# Keyboard_Joy.net
KiCad netlist of a schematic drawn in Altium Designer
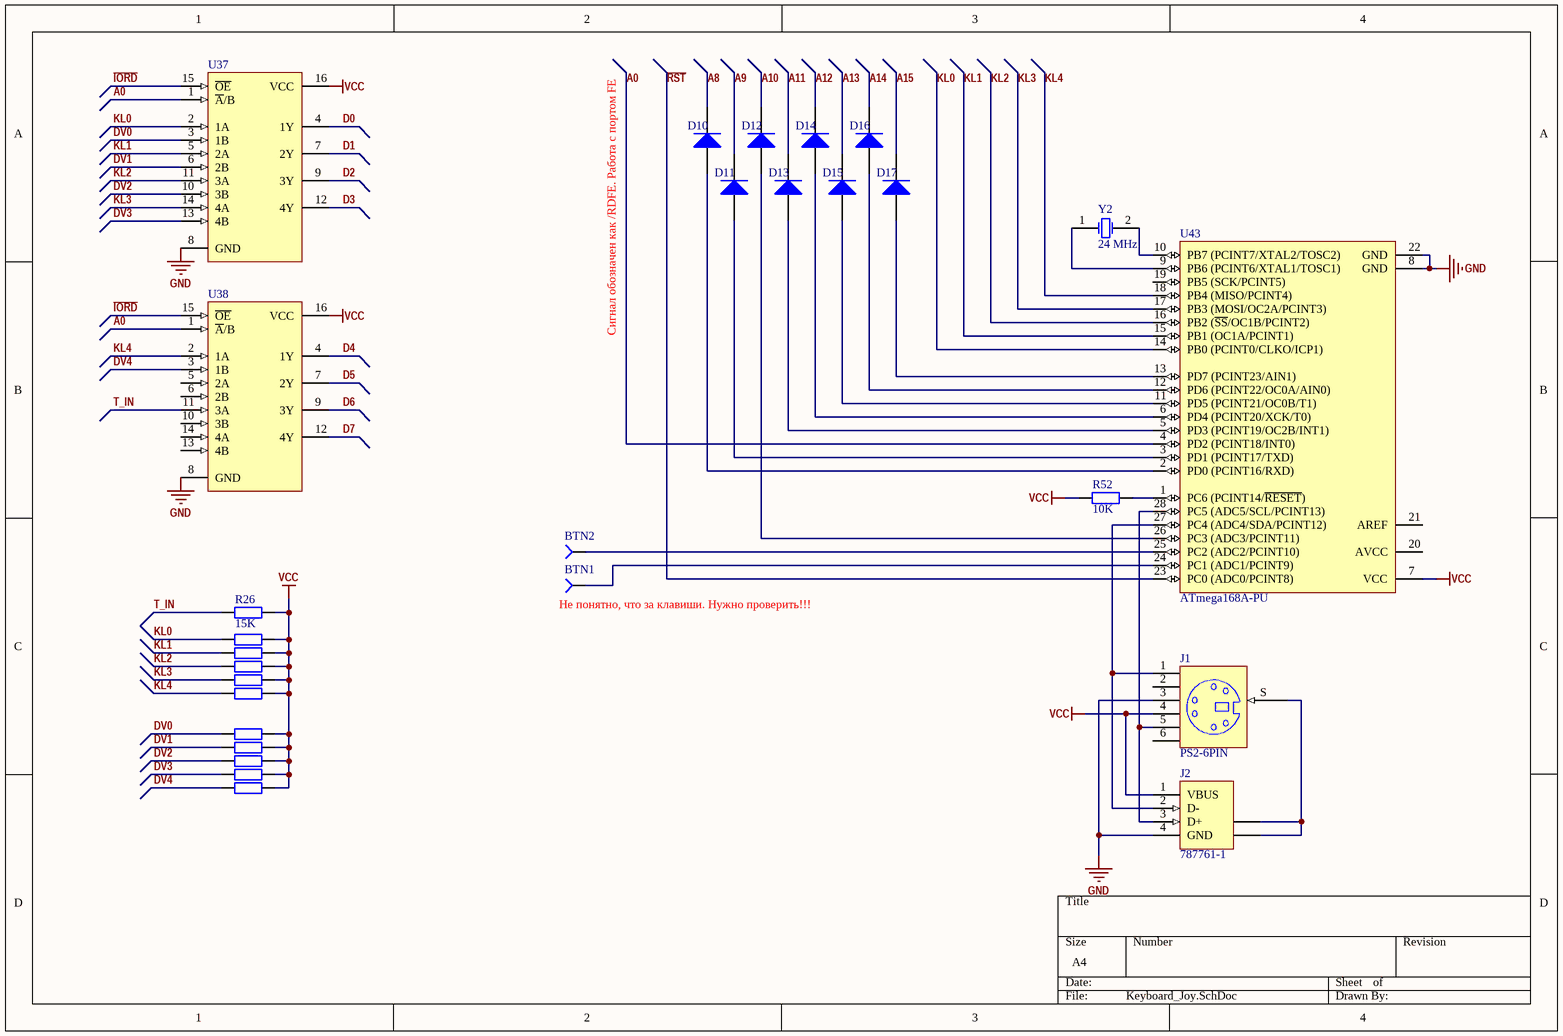
[diagram p0: Keyboard_Joy.SchDoc]

(export (version "E")
  (design (tool "Eeschema 10.0.6"))
  (components
    (comp (ref "BTN1")
      (value "Socket")
      (footprint "PIN1")
      (fields (field (name "PUBLISHER") "Altium Limited"))
      (libsource (lib "Lenin") (part "Socket"))
    )
    (comp (ref "BTN2")
      (value "Socket")
      (footprint "PIN1")
      (fields (field (name "PUBLISHER") "Altium Limited"))
      (libsource (lib "Lenin") (part "Socket"))
    )
    (comp (ref "D10")
      (value "Diode 1N4148")
      (footprint "DO-35")
      (description "High Conductance Fast Diode")
      (fields (field (name "PUBLISHER") "Altium Limited"))
      (libsource (lib "Miscellaneous Devices") (part "Diode 1N4148"))
    )
    (comp (ref "D11")
      (value "Diode 1N4148")
      (footprint "DO-35")
      (description "High Conductance Fast Diode")
      (fields (field (name "PUBLISHER") "Altium Limited"))
      (libsource (lib "Miscellaneous Devices") (part "Diode 1N4148"))
    )
    (comp (ref "D12")
      (value "Diode 1N4148")
      (footprint "DO-35")
      (description "High Conductance Fast Diode")
      (fields (field (name "PUBLISHER") "Altium Limited"))
      (libsource (lib "Miscellaneous Devices") (part "Diode 1N4148"))
    )
    (comp (ref "D13")
      (value "Diode 1N4148")
      (footprint "DO-35")
      (description "High Conductance Fast Diode")
      (fields (field (name "PUBLISHER") "Altium Limited"))
      (libsource (lib "Miscellaneous Devices") (part "Diode 1N4148"))
    )
    (comp (ref "D14")
      (value "Diode 1N4148")
      (footprint "DO-35")
      (description "High Conductance Fast Diode")
      (fields (field (name "PUBLISHER") "Altium Limited"))
      (libsource (lib "Miscellaneous Devices") (part "Diode 1N4148"))
    )
    (comp (ref "D15")
      (value "Diode 1N4148")
      (footprint "DO-35")
      (description "High Conductance Fast Diode")
      (fields (field (name "PUBLISHER") "Altium Limited"))
      (libsource (lib "Miscellaneous Devices") (part "Diode 1N4148"))
    )
    (comp (ref "D16")
      (value "Diode 1N4148")
      (footprint "DO-35")
      (description "High Conductance Fast Diode")
      (fields (field (name "PUBLISHER") "Altium Limited"))
      (libsource (lib "Miscellaneous Devices") (part "Diode 1N4148"))
    )
    (comp (ref "D17")
      (value "Diode 1N4148")
      (footprint "DO-35")
      (description "High Conductance Fast Diode")
      (fields (field (name "PUBLISHER") "Altium Limited"))
      (libsource (lib "Miscellaneous Devices") (part "Diode 1N4148"))
    )
    (comp (ref "J1")
      (value "PS2-6PIN")
      (footprint "PS2-6PIN")
      (description "6 Pin Through Hole PS2 Socket (Kycon P/N)")
      (fields (field (name "PUBLISHER") "Altium Limited"))
      (libsource (lib "Miscellaneous Connectors") (part "PS2-6PIN"))
    )
    (comp (ref "J2")
      (value "787761-1")
      (footprint "787761")
      (description "USB 1.1, Right Angle, Thru-Hole, A Type, Receptacle, 4 Position, Black")
      (fields (field (name "PUBLISHER") "Altium Limited"))
      (libsource (lib "AMP Serial Bus USB") (part "787761-1"))
    )
    (comp (ref "R26")
      (value "15K")
      (footprint "Lenin:AXIAL-0.4")
      (description "Resistor")
      (fields (field (name "Comment") "Res2") (field (name "PUBLISHER") "Altium Limited"))
      (libsource (lib "Lenin") (part "Res2"))
    )
    (comp (ref "R27")
      (value "Res2")
      (footprint "Lenin:AXIAL-0.4")
      (description "Resistor")
      (fields (field (name "PUBLISHER") "Altium Limited"))
      (libsource (lib "Lenin") (part "Res2"))
    )
    (comp (ref "R28")
      (value "Res2")
      (footprint "Lenin:AXIAL-0.4")
      (description "Resistor")
      (fields (field (name "PUBLISHER") "Altium Limited"))
      (libsource (lib "Lenin") (part "Res2"))
    )
    (comp (ref "R29")
      (value "Res2")
      (footprint "Lenin:AXIAL-0.4")
      (description "Resistor")
      (fields (field (name "PUBLISHER") "Altium Limited"))
      (libsource (lib "Lenin") (part "Res2"))
    )
    (comp (ref "R30")
      (value "Res2")
      (footprint "Lenin:AXIAL-0.4")
      (description "Resistor")
      (fields (field (name "PUBLISHER") "Altium Limited"))
      (libsource (lib "Lenin") (part "Res2"))
    )
    (comp (ref "R33")
      (value "Res2")
      (footprint "Lenin:AXIAL-0.4")
      (description "Resistor")
      (fields (field (name "PUBLISHER") "Altium Limited"))
      (libsource (lib "Lenin") (part "Res2"))
    )
    (comp (ref "R36")
      (value "Res2")
      (footprint "Lenin:AXIAL-0.4")
      (description "Resistor")
      (fields (field (name "PUBLISHER") "Altium Limited"))
      (libsource (lib "Lenin") (part "Res2"))
    )
    (comp (ref "R38")
      (value "Res2")
      (footprint "Lenin:AXIAL-0.4")
      (description "Resistor")
      (fields (field (name "PUBLISHER") "Altium Limited"))
      (libsource (lib "Lenin") (part "Res2"))
    )
    (comp (ref "R40")
      (value "Res2")
      (footprint "Lenin:AXIAL-0.4")
      (description "Resistor")
      (fields (field (name "PUBLISHER") "Altium Limited"))
      (libsource (lib "Lenin") (part "Res2"))
    )
    (comp (ref "R42")
      (value "Res2")
      (footprint "Lenin:AXIAL-0.4")
      (description "Resistor")
      (fields (field (name "PUBLISHER") "Altium Limited"))
      (libsource (lib "Lenin") (part "Res2"))
    )
    (comp (ref "R44")
      (value "Res2")
      (footprint "Lenin:AXIAL-0.4")
      (description "Resistor")
      (fields (field (name "PUBLISHER") "Altium Limited"))
      (libsource (lib "Lenin") (part "Res2"))
    )
    (comp (ref "R52")
      (value "10K")
      (footprint "Lenin:AXIAL-0.4")
      (description "Resistor")
      (fields (field (name "Comment") "Res2") (field (name "PUBLISHER") "Altium Limited"))
      (libsource (lib "") (part "Res2_1"))
    )
    (comp (ref "U37")
      (value "~")
      (footprint "N016")
      (description "Quadruple 2-Line to 1-Line Data Selector/Multiplexer with 3-State Outputs")
      (fields (field (name "PUBLISHER") "Altium Limited"))
      (libsource (lib "TI Logic Multiplexer") (part "SN74HC257N"))
    )
    (comp (ref "U38")
      (value "~")
      (footprint "N016")
      (description "Quadruple 2-Line to 1-Line Data Selector/Multiplexer with 3-State Outputs")
      (fields (field (name "PUBLISHER") "Altium Limited"))
      (libsource (lib "TI Logic Multiplexer") (part "SN74HC257N"))
    )
    (comp (ref "U43")
      (value "ATmega168A-PU")
      (footprint "28P3")
      (fields (field (name "PUBLISHER") "Altium Limited"))
      (libsource (lib "Atmel Microcontroller 8-Bit megaAVR") (part "ATmega168A-PU"))
    )
    (comp (ref "Y2")
      (value "24 MHz")
      (footprint "Lenin:HC25U")
      (description "Crystal Oscillator")
      (fields (field (name "PUBLISHER") "Altium Limited"))
      (libsource (lib "Lenin") (part "XTAL"))
    )
  )
  (nets
    (net (code "1") (name "/A0") (class "Default")
      (node (ref "U37") (pin "1") (pinfunction "~{A}/B_1") (pintype "input"))
      (node (ref "U38") (pin "1") (pinfunction "~{A}/B_1") (pintype "input"))
      (node (ref "U43") (pin "4") (pinfunction "PD2_(PCINT18/INT0)_4") (pintype "bidirectional"))
    )
    (net (code "2") (name "/A8") (class "Default")
      (node (ref "D10") (pin "2") (pinfunction "K_2") (pintype "passive"))
    )
    (net (code "3") (name "/A9") (class "Default")
      (node (ref "D11") (pin "2") (pinfunction "K_2") (pintype "passive"))
    )
    (net (code "4") (name "/A10") (class "Default")
      (node (ref "D12") (pin "2") (pinfunction "K_2") (pintype "passive"))
    )
    (net (code "5") (name "/A11") (class "Default")
      (node (ref "D13") (pin "2") (pinfunction "K_2") (pintype "passive"))
    )
    (net (code "6") (name "/A12") (class "Default")
      (node (ref "D14") (pin "2") (pinfunction "K_2") (pintype "passive"))
    )
    (net (code "7") (name "/A13") (class "Default")
      (node (ref "D15") (pin "2") (pinfunction "K_2") (pintype "passive"))
    )
    (net (code "8") (name "/A14") (class "Default")
      (node (ref "D16") (pin "2") (pinfunction "K_2") (pintype "passive"))
    )
    (net (code "9") (name "/A15") (class "Default")
      (node (ref "D17") (pin "2") (pinfunction "K_2") (pintype "passive"))
    )
    (net (code "10") (name "/D0") (class "Default")
      (node (ref "U37") (pin "4") (pinfunction "1Y_4") (pintype "tri_state"))
    )
    (net (code "11") (name "/D1") (class "Default")
      (node (ref "U37") (pin "7") (pinfunction "2Y_7") (pintype "tri_state"))
    )
    (net (code "12") (name "/D2") (class "Default")
      (node (ref "U37") (pin "9") (pinfunction "3Y_9") (pintype "tri_state"))
    )
    (net (code "13") (name "/D3") (class "Default")
      (node (ref "U37") (pin "12") (pinfunction "4Y_12") (pintype "tri_state"))
    )
    (net (code "14") (name "/D4") (class "Default")
      (node (ref "U38") (pin "4") (pinfunction "1Y_4") (pintype "tri_state"))
    )
    (net (code "15") (name "/D5") (class "Default")
      (node (ref "U38") (pin "7") (pinfunction "2Y_7") (pintype "tri_state"))
    )
    (net (code "16") (name "/D6") (class "Default")
      (node (ref "U38") (pin "9") (pinfunction "3Y_9") (pintype "tri_state"))
    )
    (net (code "17") (name "/D7") (class "Default")
      (node (ref "U38") (pin "12") (pinfunction "4Y_12") (pintype "tri_state"))
    )
    (net (code "18") (name "/DV0") (class "Default")
      (node (ref "R36") (pin "1") (pinfunction "1_1") (pintype "passive"))
      (node (ref "U37") (pin "3") (pinfunction "1B_3") (pintype "input"))
    )
    (net (code "19") (name "/DV1") (class "Default")
      (node (ref "R38") (pin "1") (pinfunction "1_1") (pintype "passive"))
      (node (ref "U37") (pin "6") (pinfunction "2B_6") (pintype "input"))
    )
    (net (code "20") (name "/DV2") (class "Default")
      (node (ref "R40") (pin "1") (pinfunction "1_1") (pintype "passive"))
      (node (ref "U37") (pin "10") (pinfunction "3B_10") (pintype "input"))
    )
    (net (code "21") (name "/DV3") (class "Default")
      (node (ref "R42") (pin "1") (pinfunction "1_1") (pintype "passive"))
      (node (ref "U37") (pin "13") (pinfunction "4B_13") (pintype "input"))
    )
    (net (code "22") (name "/DV4") (class "Default")
      (node (ref "R44") (pin "1") (pinfunction "1_1") (pintype "passive"))
      (node (ref "U38") (pin "3") (pinfunction "1B_3") (pintype "input"))
    )
    (net (code "23") (name "/KL0") (class "Default")
      (node (ref "R27") (pin "1") (pinfunction "1_1") (pintype "passive"))
      (node (ref "U37") (pin "2") (pinfunction "1A_2") (pintype "input"))
      (node (ref "U43") (pin "14") (pinfunction "PB0_(PCINT0/CLKO/ICP1)_14") (pintype "bidirectional"))
    )
    (net (code "24") (name "/KL1") (class "Default")
      (node (ref "R28") (pin "1") (pinfunction "1_1") (pintype "passive"))
      (node (ref "U37") (pin "5") (pinfunction "2A_5") (pintype "input"))
      (node (ref "U43") (pin "15") (pinfunction "PB1_(OC1A/PCINT1)_15") (pintype "bidirectional"))
    )
    (net (code "25") (name "/KL2") (class "Default")
      (node (ref "R29") (pin "1") (pinfunction "1_1") (pintype "passive"))
      (node (ref "U37") (pin "11") (pinfunction "3A_11") (pintype "input"))
      (node (ref "U43") (pin "16") (pinfunction "PB2_(~{SS}/OC1B/PCINT2)_16") (pintype "bidirectional"))
    )
    (net (code "26") (name "/KL3") (class "Default")
      (node (ref "R30") (pin "1") (pinfunction "1_1") (pintype "passive"))
      (node (ref "U37") (pin "14") (pinfunction "4A_14") (pintype "input"))
      (node (ref "U43") (pin "17") (pinfunction "PB3_(MOSI/OC2A/PCINT3)_17") (pintype "bidirectional"))
    )
    (net (code "27") (name "/KL4") (class "Default")
      (node (ref "R33") (pin "1") (pinfunction "1_1") (pintype "passive"))
      (node (ref "U38") (pin "2") (pinfunction "1A_2") (pintype "input"))
      (node (ref "U43") (pin "18") (pinfunction "PB4_(MISO/PCINT4)_18") (pintype "bidirectional"))
    )
    (net (code "28") (name "/T_IN") (class "Default")
      (node (ref "R26") (pin "1") (pinfunction "1_1") (pintype "passive"))
      (node (ref "U38") (pin "11") (pinfunction "3A_11") (pintype "input"))
    )
    (net (code "29") (name "/~{IORD}") (class "Default")
      (node (ref "U37") (pin "15") (pinfunction "~{OE}_15") (pintype "input"))
      (node (ref "U38") (pin "15") (pinfunction "~{OE}_15") (pintype "input"))
    )
    (net (code "30") (name "/~{RST}") (class "Default")
      (node (ref "U43") (pin "23") (pinfunction "PC0_(ADC0/PCINT8)_23") (pintype "bidirectional"))
    )
    (net (code "31") (name "GND") (class "Default")
      (node (ref "J1") (pin "3") (pinfunction "3_3") (pintype "passive"))
      (node (ref "J2") (pin "4") (pinfunction "GND_4") (pintype "power_in"))
      (node (ref "U37") (pin "8") (pinfunction "GND_8") (pintype "power_in"))
      (node (ref "U38") (pin "8") (pinfunction "GND_8") (pintype "power_in"))
      (node (ref "U43") (pin "22") (pinfunction "GND_22") (pintype "power_in"))
      (node (ref "U43") (pin "8") (pinfunction "GND_8") (pintype "power_in"))
    )
    (net (code "32") (name "Net-(D10-A)") (class "Default")
      (node (ref "D10") (pin "1") (pinfunction "A_1") (pintype "passive"))
      (node (ref "U43") (pin "2") (pinfunction "PD0_(PCINT16/RXD)_2") (pintype "bidirectional"))
    )
    (net (code "33") (name "Net-(D11-A)") (class "Default")
      (node (ref "D11") (pin "1") (pinfunction "A_1") (pintype "passive"))
      (node (ref "U43") (pin "3") (pinfunction "PD1_(PCINT17/TXD)_3") (pintype "bidirectional"))
    )
    (net (code "34") (name "Net-(D12-A)") (class "Default")
      (node (ref "D12") (pin "1") (pinfunction "A_1") (pintype "passive"))
      (node (ref "U43") (pin "26") (pinfunction "PC3_(ADC3/PCINT11)_26") (pintype "bidirectional"))
    )
    (net (code "35") (name "Net-(D13-A)") (class "Default")
      (node (ref "D13") (pin "1") (pinfunction "A_1") (pintype "passive"))
      (node (ref "U43") (pin "5") (pinfunction "PD3_(PCINT19/OC2B/INT1)_5") (pintype "bidirectional"))
    )
    (net (code "36") (name "Net-(D14-A)") (class "Default")
      (node (ref "D14") (pin "1") (pinfunction "A_1") (pintype "passive"))
      (node (ref "U43") (pin "6") (pinfunction "PD4_(PCINT20/XCK/T0)_6") (pintype "bidirectional"))
    )
    (net (code "37") (name "Net-(D15-A)") (class "Default")
      (node (ref "D15") (pin "1") (pinfunction "A_1") (pintype "passive"))
      (node (ref "U43") (pin "11") (pinfunction "PD5_(PCINT21/OC0B/T1)_11") (pintype "bidirectional"))
    )
    (net (code "38") (name "Net-(D16-A)") (class "Default")
      (node (ref "D16") (pin "1") (pinfunction "A_1") (pintype "passive"))
      (node (ref "U43") (pin "12") (pinfunction "PD6_(PCINT22/OC0A/AIN0)_12") (pintype "bidirectional"))
    )
    (net (code "39") (name "Net-(D17-A)") (class "Default")
      (node (ref "D17") (pin "1") (pinfunction "A_1") (pintype "passive"))
      (node (ref "U43") (pin "13") (pinfunction "PD7_(PCINT23/AIN1)_13") (pintype "bidirectional"))
    )
    (net (code "40") (name "Net-(J1-PadS)") (class "Default")
      (node (ref "J1") (pin "S") (pinfunction "S_S") (pintype "input"))
      (node (ref "J2") (pin "5") (pinfunction "SHLD_5") (pintype "passive"))
      (node (ref "J2") (pin "6") (pinfunction "SHLD_6") (pintype "passive"))
    )
    (net (code "41") (name "Net-(J2-D+)") (class "Default")
      (node (ref "J1") (pin "5") (pinfunction "5_5") (pintype "passive"))
      (node (ref "J2") (pin "3") (pinfunction "D+_3") (pintype "input"))
      (node (ref "U43") (pin "28") (pinfunction "PC5_(ADC5/SCL/PCINT13)_28") (pintype "bidirectional"))
    )
    (net (code "42") (name "Net-(J2-D-)") (class "Default")
      (node (ref "J1") (pin "1") (pinfunction "1_1") (pintype "passive"))
      (node (ref "J2") (pin "2") (pinfunction "D-_2") (pintype "input"))
      (node (ref "U43") (pin "27") (pinfunction "PC4_(ADC4/SDA/PCINT12)_27") (pintype "bidirectional"))
    )
    (net (code "43") (name "Net-(U43-PB6_(PCINT6{slash}XTAL1{slash}TOSC1))") (class "Default")
      (node (ref "U43") (pin "9") (pinfunction "PB6_(PCINT6/XTAL1/TOSC1)_9") (pintype "bidirectional"))
      (node (ref "Y2") (pin "1") (pinfunction "OSC1_1") (pintype "passive"))
    )
    (net (code "44") (name "Net-(U43-PB7_(PCINT7{slash}XTAL2{slash}TOSC2))") (class "Default")
      (node (ref "U43") (pin "10") (pinfunction "PB7_(PCINT7/XTAL2/TOSC2)_10") (pintype "bidirectional"))
      (node (ref "Y2") (pin "2") (pinfunction "OSC2_2") (pintype "passive"))
    )
    (net (code "45") (name "Net-(U43-PC1_(ADC1{slash}PCINT9))") (class "Default")
      (node (ref "BTN1") (pin "1") (pinfunction "1_1") (pintype "passive"))
      (node (ref "U43") (pin "24") (pinfunction "PC1_(ADC1/PCINT9)_24") (pintype "bidirectional"))
    )
    (net (code "46") (name "Net-(U43-PC2_(ADC2{slash}PCINT10))") (class "Default")
      (node (ref "BTN2") (pin "1") (pinfunction "1_1") (pintype "passive"))
      (node (ref "U43") (pin "25") (pinfunction "PC2_(ADC2/PCINT10)_25") (pintype "bidirectional"))
    )
    (net (code "47") (name "Net-(U43-PC6_(PCINT14{slash}~{RESET}))") (class "Default")
      (node (ref "R52") (pin "1") (pinfunction "1_1") (pintype "passive"))
      (node (ref "U43") (pin "1") (pinfunction "PC6_(PCINT14/~{RESET})_1") (pintype "bidirectional"))
    )
    (net (code "48") (name "VCC") (class "Default")
      (node (ref "J1") (pin "4") (pinfunction "4_4") (pintype "passive"))
      (node (ref "J2") (pin "1") (pinfunction "VBUS_1") (pintype "power_in"))
      (node (ref "R26") (pin "2") (pinfunction "2_2") (pintype "passive"))
      (node (ref "R27") (pin "2") (pinfunction "2_2") (pintype "passive"))
      (node (ref "R28") (pin "2") (pinfunction "2_2") (pintype "passive"))
      (node (ref "R29") (pin "2") (pinfunction "2_2") (pintype "passive"))
      (node (ref "R30") (pin "2") (pinfunction "2_2") (pintype "passive"))
      (node (ref "R33") (pin "2") (pinfunction "2_2") (pintype "passive"))
      (node (ref "R36") (pin "2") (pinfunction "2_2") (pintype "passive"))
      (node (ref "R38") (pin "2") (pinfunction "2_2") (pintype "passive"))
      (node (ref "R40") (pin "2") (pinfunction "2_2") (pintype "passive"))
      (node (ref "R42") (pin "2") (pinfunction "2_2") (pintype "passive"))
      (node (ref "R44") (pin "2") (pinfunction "2_2") (pintype "passive"))
      (node (ref "R52") (pin "2") (pinfunction "2_2") (pintype "passive"))
      (node (ref "U37") (pin "16") (pinfunction "VCC_16") (pintype "power_in"))
      (node (ref "U38") (pin "16") (pinfunction "VCC_16") (pintype "power_in"))
      (node (ref "U43") (pin "7") (pinfunction "VCC_7") (pintype "power_in"))
    )
    (net (code "49") (name "unconnected-(J1-Pad2)") (class "Default")
      (node (ref "J1") (pin "2") (pinfunction "2_2") (pintype "passive"))
    )
    (net (code "50") (name "unconnected-(J1-Pad6)") (class "Default")
      (node (ref "J1") (pin "6") (pinfunction "6_6") (pintype "passive"))
    )
    (net (code "51") (name "unconnected-(U38-2A-Pad5)") (class "Default")
      (node (ref "U38") (pin "5") (pinfunction "2A_5") (pintype "input"))
    )
    (net (code "52") (name "unconnected-(U38-2B-Pad6)") (class "Default")
      (node (ref "U38") (pin "6") (pinfunction "2B_6") (pintype "input"))
    )
    (net (code "53") (name "unconnected-(U38-3B-Pad10)") (class "Default")
      (node (ref "U38") (pin "10") (pinfunction "3B_10") (pintype "input"))
    )
    (net (code "54") (name "unconnected-(U38-4A-Pad14)") (class "Default")
      (node (ref "U38") (pin "14") (pinfunction "4A_14") (pintype "input"))
    )
    (net (code "55") (name "unconnected-(U38-4B-Pad13)") (class "Default")
      (node (ref "U38") (pin "13") (pinfunction "4B_13") (pintype "input"))
    )
    (net (code "56") (name "unconnected-(U43-AREF-Pad21)") (class "Default")
      (node (ref "U43") (pin "21") (pinfunction "AREF_21") (pintype "power_in"))
    )
    (net (code "57") (name "unconnected-(U43-AVCC-Pad20)") (class "Default")
      (node (ref "U43") (pin "20") (pinfunction "AVCC_20") (pintype "power_in"))
    )
    (net (code "58") (name "unconnected-(U43-PB5_(SCK{slash}PCINT5)-Pad19)") (class "Default")
      (node (ref "U43") (pin "19") (pinfunction "PB5_(SCK/PCINT5)_19") (pintype "bidirectional"))
    )
  )
)
